# WS2812_MATRIX_8.net
KiCad netlist of a schematic drawn in Altium Designer
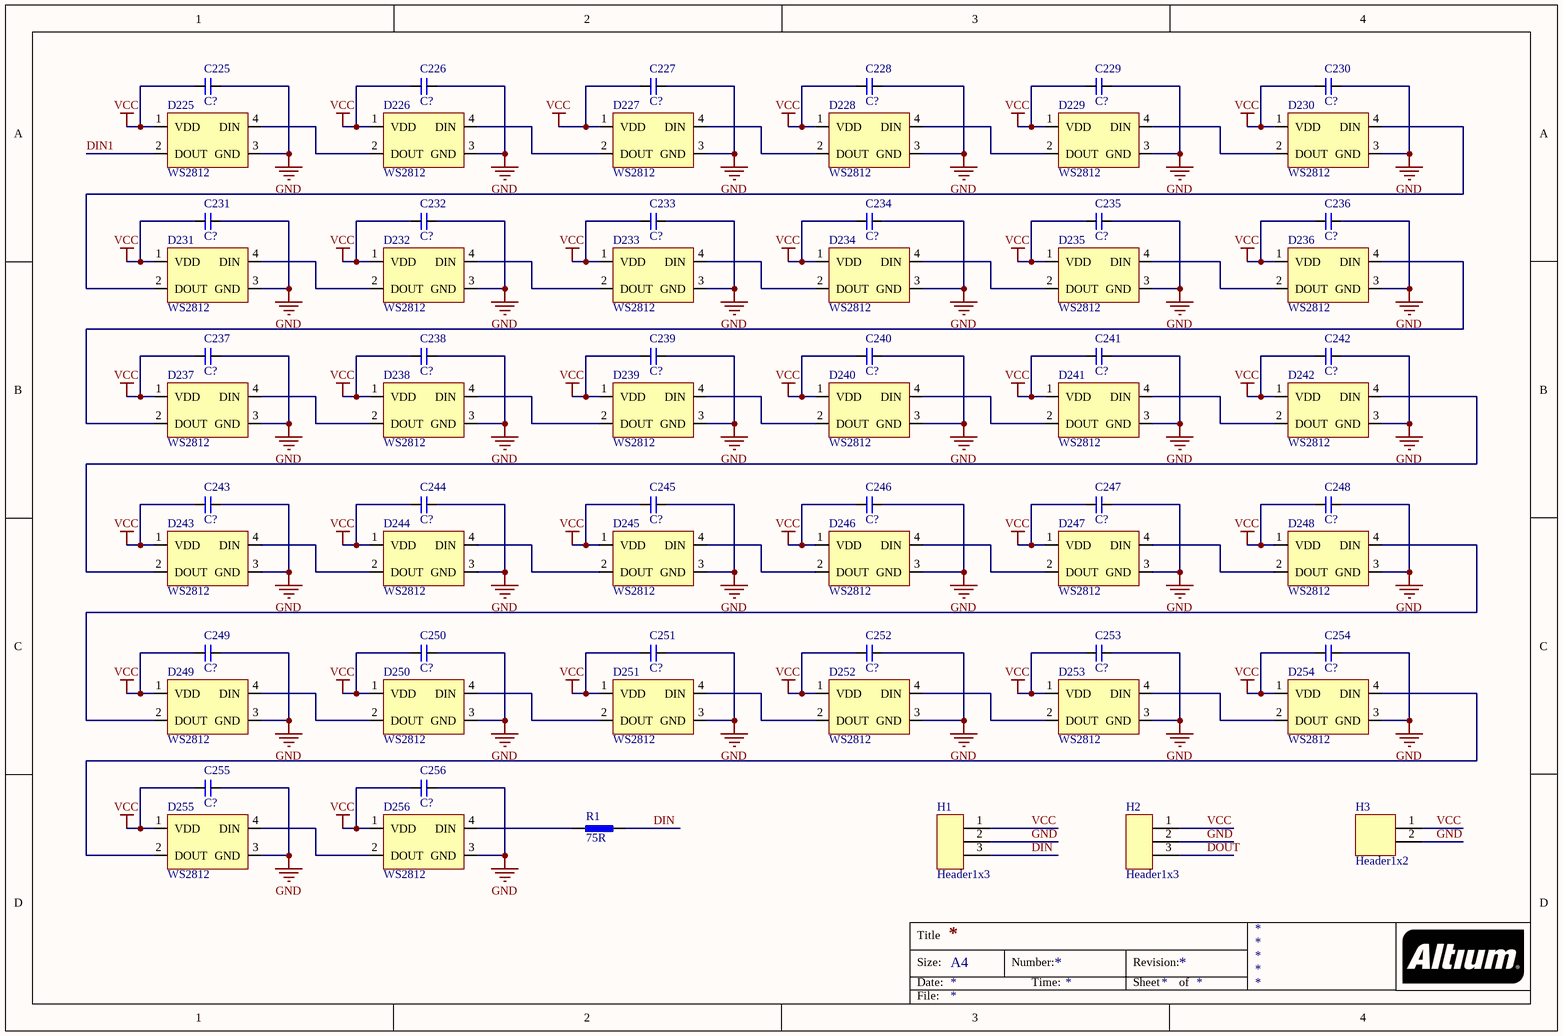
[diagram p0: WS2812_MATRIX_8.SchDoc]

(export (version "E")
  (design (tool "Eeschema 10.0.6"))
  (components
    (comp (ref "C225")
      (value "C?")
      (footprint "C0603")
      (description "Cap")
      (libsource (lib "SCH_Bacsic") (part "CAP"))
    )
    (comp (ref "C226")
      (value "C?")
      (footprint "C0603")
      (description "Cap")
      (libsource (lib "SCH_Bacsic") (part "CAP"))
    )
    (comp (ref "C227")
      (value "C?")
      (footprint "C0603")
      (description "Cap")
      (libsource (lib "SCH_Bacsic") (part "CAP"))
    )
    (comp (ref "C228")
      (value "C?")
      (footprint "C0603")
      (description "Cap")
      (libsource (lib "SCH_Bacsic") (part "CAP"))
    )
    (comp (ref "C229")
      (value "C?")
      (footprint "C0603")
      (description "Cap")
      (libsource (lib "SCH_Bacsic") (part "CAP"))
    )
    (comp (ref "C230")
      (value "C?")
      (footprint "C0603")
      (description "Cap")
      (libsource (lib "SCH_Bacsic") (part "CAP"))
    )
    (comp (ref "C231")
      (value "C?")
      (footprint "C0603")
      (description "Cap")
      (libsource (lib "SCH_Bacsic") (part "CAP"))
    )
    (comp (ref "C232")
      (value "C?")
      (footprint "C0603")
      (description "Cap")
      (libsource (lib "SCH_Bacsic") (part "CAP"))
    )
    (comp (ref "C233")
      (value "C?")
      (footprint "C0603")
      (description "Cap")
      (libsource (lib "SCH_Bacsic") (part "CAP"))
    )
    (comp (ref "C234")
      (value "C?")
      (footprint "C0603")
      (description "Cap")
      (libsource (lib "SCH_Bacsic") (part "CAP"))
    )
    (comp (ref "C235")
      (value "C?")
      (footprint "C0603")
      (description "Cap")
      (libsource (lib "SCH_Bacsic") (part "CAP"))
    )
    (comp (ref "C236")
      (value "C?")
      (footprint "C0603")
      (description "Cap")
      (libsource (lib "SCH_Bacsic") (part "CAP"))
    )
    (comp (ref "C237")
      (value "C?")
      (footprint "C0603")
      (description "Cap")
      (libsource (lib "SCH_Bacsic") (part "CAP"))
    )
    (comp (ref "C238")
      (value "C?")
      (footprint "C0603")
      (description "Cap")
      (libsource (lib "SCH_Bacsic") (part "CAP"))
    )
    (comp (ref "C239")
      (value "C?")
      (footprint "C0603")
      (description "Cap")
      (libsource (lib "SCH_Bacsic") (part "CAP"))
    )
    (comp (ref "C240")
      (value "C?")
      (footprint "C0603")
      (description "Cap")
      (libsource (lib "SCH_Bacsic") (part "CAP"))
    )
    (comp (ref "C241")
      (value "C?")
      (footprint "C0603")
      (description "Cap")
      (libsource (lib "SCH_Bacsic") (part "CAP"))
    )
    (comp (ref "C242")
      (value "C?")
      (footprint "C0603")
      (description "Cap")
      (libsource (lib "SCH_Bacsic") (part "CAP"))
    )
    (comp (ref "C243")
      (value "C?")
      (footprint "C0603")
      (description "Cap")
      (libsource (lib "SCH_Bacsic") (part "CAP"))
    )
    (comp (ref "C244")
      (value "C?")
      (footprint "C0603")
      (description "Cap")
      (libsource (lib "SCH_Bacsic") (part "CAP"))
    )
    (comp (ref "C245")
      (value "C?")
      (footprint "C0603")
      (description "Cap")
      (libsource (lib "SCH_Bacsic") (part "CAP"))
    )
    (comp (ref "C246")
      (value "C?")
      (footprint "C0603")
      (description "Cap")
      (libsource (lib "SCH_Bacsic") (part "CAP"))
    )
    (comp (ref "C247")
      (value "C?")
      (footprint "C0603")
      (description "Cap")
      (libsource (lib "SCH_Bacsic") (part "CAP"))
    )
    (comp (ref "C248")
      (value "C?")
      (footprint "C0603")
      (description "Cap")
      (libsource (lib "SCH_Bacsic") (part "CAP"))
    )
    (comp (ref "C249")
      (value "C?")
      (footprint "C0603")
      (description "Cap")
      (libsource (lib "SCH_Bacsic") (part "CAP"))
    )
    (comp (ref "C250")
      (value "C?")
      (footprint "C0603")
      (description "Cap")
      (libsource (lib "SCH_Bacsic") (part "CAP"))
    )
    (comp (ref "C251")
      (value "C?")
      (footprint "C0603")
      (description "Cap")
      (libsource (lib "SCH_Bacsic") (part "CAP"))
    )
    (comp (ref "C252")
      (value "C?")
      (footprint "C0603")
      (description "Cap")
      (libsource (lib "SCH_Bacsic") (part "CAP"))
    )
    (comp (ref "C253")
      (value "C?")
      (footprint "C0603")
      (description "Cap")
      (libsource (lib "SCH_Bacsic") (part "CAP"))
    )
    (comp (ref "C254")
      (value "C?")
      (footprint "C0603")
      (description "Cap")
      (libsource (lib "SCH_Bacsic") (part "CAP"))
    )
    (comp (ref "C255")
      (value "C?")
      (footprint "C0603")
      (description "Cap")
      (libsource (lib "SCH_Bacsic") (part "CAP"))
    )
    (comp (ref "C256")
      (value "C?")
      (footprint "C0603")
      (description "Cap")
      (libsource (lib "SCH_Bacsic") (part "CAP"))
    )
    (comp (ref "D225")
      (value "WS2812")
      (footprint "WS2812_3528")
      (libsource (lib "SCH_Bacsic") (part "WS2812"))
    )
    (comp (ref "D226")
      (value "WS2812")
      (footprint "WS2812_3528")
      (libsource (lib "SCH_Bacsic") (part "WS2812"))
    )
    (comp (ref "D227")
      (value "WS2812")
      (footprint "WS2812_3528")
      (libsource (lib "SCH_Bacsic") (part "WS2812"))
    )
    (comp (ref "D228")
      (value "WS2812")
      (footprint "WS2812_3528")
      (libsource (lib "SCH_Bacsic") (part "WS2812"))
    )
    (comp (ref "D229")
      (value "WS2812")
      (footprint "WS2812_3528")
      (libsource (lib "SCH_Bacsic") (part "WS2812"))
    )
    (comp (ref "D230")
      (value "WS2812")
      (footprint "WS2812_3528")
      (libsource (lib "SCH_Bacsic") (part "WS2812"))
    )
    (comp (ref "D231")
      (value "WS2812")
      (footprint "WS2812_3528")
      (libsource (lib "SCH_Bacsic") (part "WS2812"))
    )
    (comp (ref "D232")
      (value "WS2812")
      (footprint "WS2812_3528")
      (libsource (lib "SCH_Bacsic") (part "WS2812"))
    )
    (comp (ref "D233")
      (value "WS2812")
      (footprint "WS2812_3528")
      (libsource (lib "SCH_Bacsic") (part "WS2812"))
    )
    (comp (ref "D234")
      (value "WS2812")
      (footprint "WS2812_3528")
      (libsource (lib "SCH_Bacsic") (part "WS2812"))
    )
    (comp (ref "D235")
      (value "WS2812")
      (footprint "WS2812_3528")
      (libsource (lib "SCH_Bacsic") (part "WS2812"))
    )
    (comp (ref "D236")
      (value "WS2812")
      (footprint "WS2812_3528")
      (libsource (lib "SCH_Bacsic") (part "WS2812"))
    )
    (comp (ref "D237")
      (value "WS2812")
      (footprint "WS2812_3528")
      (libsource (lib "SCH_Bacsic") (part "WS2812"))
    )
    (comp (ref "D238")
      (value "WS2812")
      (footprint "WS2812_3528")
      (libsource (lib "SCH_Bacsic") (part "WS2812"))
    )
    (comp (ref "D239")
      (value "WS2812")
      (footprint "WS2812_3528")
      (libsource (lib "SCH_Bacsic") (part "WS2812"))
    )
    (comp (ref "D240")
      (value "WS2812")
      (footprint "WS2812_3528")
      (libsource (lib "SCH_Bacsic") (part "WS2812"))
    )
    (comp (ref "D241")
      (value "WS2812")
      (footprint "WS2812_3528")
      (libsource (lib "SCH_Bacsic") (part "WS2812"))
    )
    (comp (ref "D242")
      (value "WS2812")
      (footprint "WS2812_3528")
      (libsource (lib "SCH_Bacsic") (part "WS2812"))
    )
    (comp (ref "D243")
      (value "WS2812")
      (footprint "WS2812_3528")
      (libsource (lib "SCH_Bacsic") (part "WS2812"))
    )
    (comp (ref "D244")
      (value "WS2812")
      (footprint "WS2812_3528")
      (libsource (lib "SCH_Bacsic") (part "WS2812"))
    )
    (comp (ref "D245")
      (value "WS2812")
      (footprint "WS2812_3528")
      (libsource (lib "SCH_Bacsic") (part "WS2812"))
    )
    (comp (ref "D246")
      (value "WS2812")
      (footprint "WS2812_3528")
      (libsource (lib "SCH_Bacsic") (part "WS2812"))
    )
    (comp (ref "D247")
      (value "WS2812")
      (footprint "WS2812_3528")
      (libsource (lib "SCH_Bacsic") (part "WS2812"))
    )
    (comp (ref "D248")
      (value "WS2812")
      (footprint "WS2812_3528")
      (libsource (lib "SCH_Bacsic") (part "WS2812"))
    )
    (comp (ref "D249")
      (value "WS2812")
      (footprint "WS2812_3528")
      (libsource (lib "SCH_Bacsic") (part "WS2812"))
    )
    (comp (ref "D250")
      (value "WS2812")
      (footprint "WS2812_3528")
      (libsource (lib "SCH_Bacsic") (part "WS2812"))
    )
    (comp (ref "D251")
      (value "WS2812")
      (footprint "WS2812_3528")
      (libsource (lib "SCH_Bacsic") (part "WS2812"))
    )
    (comp (ref "D252")
      (value "WS2812")
      (footprint "WS2812_3528")
      (libsource (lib "SCH_Bacsic") (part "WS2812"))
    )
    (comp (ref "D253")
      (value "WS2812")
      (footprint "WS2812_3528")
      (libsource (lib "SCH_Bacsic") (part "WS2812"))
    )
    (comp (ref "D254")
      (value "WS2812")
      (footprint "WS2812_3528")
      (libsource (lib "SCH_Bacsic") (part "WS2812"))
    )
    (comp (ref "D255")
      (value "WS2812")
      (footprint "WS2812_3528")
      (libsource (lib "SCH_Bacsic") (part "WS2812"))
    )
    (comp (ref "D256")
      (value "WS2812")
      (footprint "WS2812_3528")
      (libsource (lib "SCH_Bacsic") (part "WS2812"))
    )
    (comp (ref "H1")
      (value "Header1x3")
      (footprint "HDR1X3_2.54_NO_HOLE")
      (libsource (lib "SCH_Connector") (part "Header1x3"))
    )
    (comp (ref "H2")
      (value "Header1x3")
      (footprint "HDR1X3_2.54_NO_HOLE")
      (libsource (lib "SCH_Connector") (part "Header1x3"))
    )
    (comp (ref "H3")
      (value "Header1x2")
      (footprint "BATIN")
      (libsource (lib "SCH_Connector") (part "Header1x2"))
    )
    (comp (ref "R1") (value "75R") (footprint "R0603") (libsource (lib "SCH_Bacsic") (part "RES")))
  )
  (nets
    (net (code "1") (name "/DIN") (class "Default")
      (node (ref "H1") (pin "3") (pintype "passive"))
      (node (ref "R1") (pin "2") (pintype "passive"))
    )
    (net (code "2") (name "/DIN1") (class "Default")
      (node (ref "D225") (pin "2") (pinfunction "DOUT_2") (pintype "passive"))
    )
    (net (code "3") (name "/DOUT") (class "Default") (node (ref "H2") (pin "3") (pintype "passive")))
    (net (code "4") (name "GND") (class "Default")
      (node (ref "C225") (pin "2") (pintype "passive"))
      (node (ref "C226") (pin "2") (pintype "passive"))
      (node (ref "C227") (pin "2") (pintype "passive"))
      (node (ref "C228") (pin "2") (pintype "passive"))
      (node (ref "C229") (pin "2") (pintype "passive"))
      (node (ref "C230") (pin "2") (pintype "passive"))
      (node (ref "C231") (pin "2") (pintype "passive"))
      (node (ref "C232") (pin "2") (pintype "passive"))
      (node (ref "C233") (pin "2") (pintype "passive"))
      (node (ref "C234") (pin "2") (pintype "passive"))
      (node (ref "C235") (pin "2") (pintype "passive"))
      (node (ref "C236") (pin "2") (pintype "passive"))
      (node (ref "C237") (pin "2") (pintype "passive"))
      (node (ref "C238") (pin "2") (pintype "passive"))
      (node (ref "C239") (pin "2") (pintype "passive"))
      (node (ref "C240") (pin "2") (pintype "passive"))
      (node (ref "C241") (pin "2") (pintype "passive"))
      (node (ref "C242") (pin "2") (pintype "passive"))
      (node (ref "C243") (pin "2") (pintype "passive"))
      (node (ref "C244") (pin "2") (pintype "passive"))
      (node (ref "C245") (pin "2") (pintype "passive"))
      (node (ref "C246") (pin "2") (pintype "passive"))
      (node (ref "C247") (pin "2") (pintype "passive"))
      (node (ref "C248") (pin "2") (pintype "passive"))
      (node (ref "C249") (pin "2") (pintype "passive"))
      (node (ref "C250") (pin "2") (pintype "passive"))
      (node (ref "C251") (pin "2") (pintype "passive"))
      (node (ref "C252") (pin "2") (pintype "passive"))
      (node (ref "C253") (pin "2") (pintype "passive"))
      (node (ref "C254") (pin "2") (pintype "passive"))
      (node (ref "C255") (pin "2") (pintype "passive"))
      (node (ref "C256") (pin "2") (pintype "passive"))
      (node (ref "D225") (pin "3") (pinfunction "GND_3") (pintype "passive"))
      (node (ref "D226") (pin "3") (pinfunction "GND_3") (pintype "passive"))
      (node (ref "D227") (pin "3") (pinfunction "GND_3") (pintype "passive"))
      (node (ref "D228") (pin "3") (pinfunction "GND_3") (pintype "passive"))
      (node (ref "D229") (pin "3") (pinfunction "GND_3") (pintype "passive"))
      (node (ref "D230") (pin "3") (pinfunction "GND_3") (pintype "passive"))
      (node (ref "D231") (pin "3") (pinfunction "GND_3") (pintype "passive"))
      (node (ref "D232") (pin "3") (pinfunction "GND_3") (pintype "passive"))
      (node (ref "D233") (pin "3") (pinfunction "GND_3") (pintype "passive"))
      (node (ref "D234") (pin "3") (pinfunction "GND_3") (pintype "passive"))
      (node (ref "D235") (pin "3") (pinfunction "GND_3") (pintype "passive"))
      (node (ref "D236") (pin "3") (pinfunction "GND_3") (pintype "passive"))
      (node (ref "D237") (pin "3") (pinfunction "GND_3") (pintype "passive"))
      (node (ref "D238") (pin "3") (pinfunction "GND_3") (pintype "passive"))
      (node (ref "D239") (pin "3") (pinfunction "GND_3") (pintype "passive"))
      (node (ref "D240") (pin "3") (pinfunction "GND_3") (pintype "passive"))
      (node (ref "D241") (pin "3") (pinfunction "GND_3") (pintype "passive"))
      (node (ref "D242") (pin "3") (pinfunction "GND_3") (pintype "passive"))
      (node (ref "D243") (pin "3") (pinfunction "GND_3") (pintype "passive"))
      (node (ref "D244") (pin "3") (pinfunction "GND_3") (pintype "passive"))
      (node (ref "D245") (pin "3") (pinfunction "GND_3") (pintype "passive"))
      (node (ref "D246") (pin "3") (pinfunction "GND_3") (pintype "passive"))
      (node (ref "D247") (pin "3") (pinfunction "GND_3") (pintype "passive"))
      (node (ref "D248") (pin "3") (pinfunction "GND_3") (pintype "passive"))
      (node (ref "D249") (pin "3") (pinfunction "GND_3") (pintype "passive"))
      (node (ref "D250") (pin "3") (pinfunction "GND_3") (pintype "passive"))
      (node (ref "D251") (pin "3") (pinfunction "GND_3") (pintype "passive"))
      (node (ref "D252") (pin "3") (pinfunction "GND_3") (pintype "passive"))
      (node (ref "D253") (pin "3") (pinfunction "GND_3") (pintype "passive"))
      (node (ref "D254") (pin "3") (pinfunction "GND_3") (pintype "passive"))
      (node (ref "D255") (pin "3") (pinfunction "GND_3") (pintype "passive"))
      (node (ref "D256") (pin "3") (pinfunction "GND_3") (pintype "passive"))
      (node (ref "H1") (pin "2") (pintype "passive"))
      (node (ref "H2") (pin "2") (pintype "passive"))
      (node (ref "H3") (pin "2") (pintype "passive"))
    )
    (net (code "5") (name "Net-(D225-DIN)") (class "Default")
      (node (ref "D225") (pin "4") (pinfunction "DIN_4") (pintype "passive"))
      (node (ref "D226") (pin "2") (pinfunction "DOUT_2") (pintype "passive"))
    )
    (net (code "6") (name "Net-(D226-DIN)") (class "Default")
      (node (ref "D226") (pin "4") (pinfunction "DIN_4") (pintype "passive"))
      (node (ref "D227") (pin "2") (pinfunction "DOUT_2") (pintype "passive"))
    )
    (net (code "7") (name "Net-(D227-DIN)") (class "Default")
      (node (ref "D227") (pin "4") (pinfunction "DIN_4") (pintype "passive"))
      (node (ref "D228") (pin "2") (pinfunction "DOUT_2") (pintype "passive"))
    )
    (net (code "8") (name "Net-(D228-DIN)") (class "Default")
      (node (ref "D228") (pin "4") (pinfunction "DIN_4") (pintype "passive"))
      (node (ref "D229") (pin "2") (pinfunction "DOUT_2") (pintype "passive"))
    )
    (net (code "9") (name "Net-(D229-DIN)") (class "Default")
      (node (ref "D229") (pin "4") (pinfunction "DIN_4") (pintype "passive"))
      (node (ref "D230") (pin "2") (pinfunction "DOUT_2") (pintype "passive"))
    )
    (net (code "10") (name "Net-(D230-DIN)") (class "Default")
      (node (ref "D230") (pin "4") (pinfunction "DIN_4") (pintype "passive"))
      (node (ref "D231") (pin "2") (pinfunction "DOUT_2") (pintype "passive"))
    )
    (net (code "11") (name "Net-(D231-DIN)") (class "Default")
      (node (ref "D231") (pin "4") (pinfunction "DIN_4") (pintype "passive"))
      (node (ref "D232") (pin "2") (pinfunction "DOUT_2") (pintype "passive"))
    )
    (net (code "12") (name "Net-(D232-DIN)") (class "Default")
      (node (ref "D232") (pin "4") (pinfunction "DIN_4") (pintype "passive"))
      (node (ref "D233") (pin "2") (pinfunction "DOUT_2") (pintype "passive"))
    )
    (net (code "13") (name "Net-(D233-DIN)") (class "Default")
      (node (ref "D233") (pin "4") (pinfunction "DIN_4") (pintype "passive"))
      (node (ref "D234") (pin "2") (pinfunction "DOUT_2") (pintype "passive"))
    )
    (net (code "14") (name "Net-(D234-DIN)") (class "Default")
      (node (ref "D234") (pin "4") (pinfunction "DIN_4") (pintype "passive"))
      (node (ref "D235") (pin "2") (pinfunction "DOUT_2") (pintype "passive"))
    )
    (net (code "15") (name "Net-(D235-DIN)") (class "Default")
      (node (ref "D235") (pin "4") (pinfunction "DIN_4") (pintype "passive"))
      (node (ref "D236") (pin "2") (pinfunction "DOUT_2") (pintype "passive"))
    )
    (net (code "16") (name "Net-(D236-DIN)") (class "Default")
      (node (ref "D236") (pin "4") (pinfunction "DIN_4") (pintype "passive"))
      (node (ref "D237") (pin "2") (pinfunction "DOUT_2") (pintype "passive"))
    )
    (net (code "17") (name "Net-(D237-DIN)") (class "Default")
      (node (ref "D237") (pin "4") (pinfunction "DIN_4") (pintype "passive"))
      (node (ref "D238") (pin "2") (pinfunction "DOUT_2") (pintype "passive"))
    )
    (net (code "18") (name "Net-(D238-DIN)") (class "Default")
      (node (ref "D238") (pin "4") (pinfunction "DIN_4") (pintype "passive"))
      (node (ref "D239") (pin "2") (pinfunction "DOUT_2") (pintype "passive"))
    )
    (net (code "19") (name "Net-(D239-DIN)") (class "Default")
      (node (ref "D239") (pin "4") (pinfunction "DIN_4") (pintype "passive"))
      (node (ref "D240") (pin "2") (pinfunction "DOUT_2") (pintype "passive"))
    )
    (net (code "20") (name "Net-(D240-DIN)") (class "Default")
      (node (ref "D240") (pin "4") (pinfunction "DIN_4") (pintype "passive"))
      (node (ref "D241") (pin "2") (pinfunction "DOUT_2") (pintype "passive"))
    )
    (net (code "21") (name "Net-(D241-DIN)") (class "Default")
      (node (ref "D241") (pin "4") (pinfunction "DIN_4") (pintype "passive"))
      (node (ref "D242") (pin "2") (pinfunction "DOUT_2") (pintype "passive"))
    )
    (net (code "22") (name "Net-(D242-DIN)") (class "Default")
      (node (ref "D242") (pin "4") (pinfunction "DIN_4") (pintype "passive"))
      (node (ref "D243") (pin "2") (pinfunction "DOUT_2") (pintype "passive"))
    )
    (net (code "23") (name "Net-(D243-DIN)") (class "Default")
      (node (ref "D243") (pin "4") (pinfunction "DIN_4") (pintype "passive"))
      (node (ref "D244") (pin "2") (pinfunction "DOUT_2") (pintype "passive"))
    )
    (net (code "24") (name "Net-(D244-DIN)") (class "Default")
      (node (ref "D244") (pin "4") (pinfunction "DIN_4") (pintype "passive"))
      (node (ref "D245") (pin "2") (pinfunction "DOUT_2") (pintype "passive"))
    )
    (net (code "25") (name "Net-(D245-DIN)") (class "Default")
      (node (ref "D245") (pin "4") (pinfunction "DIN_4") (pintype "passive"))
      (node (ref "D246") (pin "2") (pinfunction "DOUT_2") (pintype "passive"))
    )
    (net (code "26") (name "Net-(D246-DIN)") (class "Default")
      (node (ref "D246") (pin "4") (pinfunction "DIN_4") (pintype "passive"))
      (node (ref "D247") (pin "2") (pinfunction "DOUT_2") (pintype "passive"))
    )
    (net (code "27") (name "Net-(D247-DIN)") (class "Default")
      (node (ref "D247") (pin "4") (pinfunction "DIN_4") (pintype "passive"))
      (node (ref "D248") (pin "2") (pinfunction "DOUT_2") (pintype "passive"))
    )
    (net (code "28") (name "Net-(D248-DIN)") (class "Default")
      (node (ref "D248") (pin "4") (pinfunction "DIN_4") (pintype "passive"))
      (node (ref "D249") (pin "2") (pinfunction "DOUT_2") (pintype "passive"))
    )
    (net (code "29") (name "Net-(D249-DIN)") (class "Default")
      (node (ref "D249") (pin "4") (pinfunction "DIN_4") (pintype "passive"))
      (node (ref "D250") (pin "2") (pinfunction "DOUT_2") (pintype "passive"))
    )
    (net (code "30") (name "Net-(D250-DIN)") (class "Default")
      (node (ref "D250") (pin "4") (pinfunction "DIN_4") (pintype "passive"))
      (node (ref "D251") (pin "2") (pinfunction "DOUT_2") (pintype "passive"))
    )
    (net (code "31") (name "Net-(D251-DIN)") (class "Default")
      (node (ref "D251") (pin "4") (pinfunction "DIN_4") (pintype "passive"))
      (node (ref "D252") (pin "2") (pinfunction "DOUT_2") (pintype "passive"))
    )
    (net (code "32") (name "Net-(D252-DIN)") (class "Default")
      (node (ref "D252") (pin "4") (pinfunction "DIN_4") (pintype "passive"))
      (node (ref "D253") (pin "2") (pinfunction "DOUT_2") (pintype "passive"))
    )
    (net (code "33") (name "Net-(D253-DIN)") (class "Default")
      (node (ref "D253") (pin "4") (pinfunction "DIN_4") (pintype "passive"))
      (node (ref "D254") (pin "2") (pinfunction "DOUT_2") (pintype "passive"))
    )
    (net (code "34") (name "Net-(D254-DIN)") (class "Default")
      (node (ref "D254") (pin "4") (pinfunction "DIN_4") (pintype "passive"))
      (node (ref "D255") (pin "2") (pinfunction "DOUT_2") (pintype "passive"))
    )
    (net (code "35") (name "Net-(D255-DIN)") (class "Default")
      (node (ref "D255") (pin "4") (pinfunction "DIN_4") (pintype "passive"))
      (node (ref "D256") (pin "2") (pinfunction "DOUT_2") (pintype "passive"))
    )
    (net (code "36") (name "Net-(D256-DIN)") (class "Default")
      (node (ref "D256") (pin "4") (pinfunction "DIN_4") (pintype "passive"))
      (node (ref "R1") (pin "1") (pintype "passive"))
    )
    (net (code "37") (name "VCC") (class "Default")
      (node (ref "C225") (pin "1") (pintype "passive"))
      (node (ref "C226") (pin "1") (pintype "passive"))
      (node (ref "C227") (pin "1") (pintype "passive"))
      (node (ref "C228") (pin "1") (pintype "passive"))
      (node (ref "C229") (pin "1") (pintype "passive"))
      (node (ref "C230") (pin "1") (pintype "passive"))
      (node (ref "C231") (pin "1") (pintype "passive"))
      (node (ref "C232") (pin "1") (pintype "passive"))
      (node (ref "C233") (pin "1") (pintype "passive"))
      (node (ref "C234") (pin "1") (pintype "passive"))
      (node (ref "C235") (pin "1") (pintype "passive"))
      (node (ref "C236") (pin "1") (pintype "passive"))
      (node (ref "C237") (pin "1") (pintype "passive"))
      (node (ref "C238") (pin "1") (pintype "passive"))
      (node (ref "C239") (pin "1") (pintype "passive"))
      (node (ref "C240") (pin "1") (pintype "passive"))
      (node (ref "C241") (pin "1") (pintype "passive"))
      (node (ref "C242") (pin "1") (pintype "passive"))
      (node (ref "C243") (pin "1") (pintype "passive"))
      (node (ref "C244") (pin "1") (pintype "passive"))
      (node (ref "C245") (pin "1") (pintype "passive"))
      (node (ref "C246") (pin "1") (pintype "passive"))
      (node (ref "C247") (pin "1") (pintype "passive"))
      (node (ref "C248") (pin "1") (pintype "passive"))
      (node (ref "C249") (pin "1") (pintype "passive"))
      (node (ref "C250") (pin "1") (pintype "passive"))
      (node (ref "C251") (pin "1") (pintype "passive"))
      (node (ref "C252") (pin "1") (pintype "passive"))
      (node (ref "C253") (pin "1") (pintype "passive"))
      (node (ref "C254") (pin "1") (pintype "passive"))
      (node (ref "C255") (pin "1") (pintype "passive"))
      (node (ref "C256") (pin "1") (pintype "passive"))
      (node (ref "D225") (pin "1") (pinfunction "VDD_1") (pintype "passive"))
      (node (ref "D226") (pin "1") (pinfunction "VDD_1") (pintype "passive"))
      (node (ref "D227") (pin "1") (pinfunction "VDD_1") (pintype "passive"))
      (node (ref "D228") (pin "1") (pinfunction "VDD_1") (pintype "passive"))
      (node (ref "D229") (pin "1") (pinfunction "VDD_1") (pintype "passive"))
      (node (ref "D230") (pin "1") (pinfunction "VDD_1") (pintype "passive"))
      (node (ref "D231") (pin "1") (pinfunction "VDD_1") (pintype "passive"))
      (node (ref "D232") (pin "1") (pinfunction "VDD_1") (pintype "passive"))
      (node (ref "D233") (pin "1") (pinfunction "VDD_1") (pintype "passive"))
      (node (ref "D234") (pin "1") (pinfunction "VDD_1") (pintype "passive"))
      (node (ref "D235") (pin "1") (pinfunction "VDD_1") (pintype "passive"))
      (node (ref "D236") (pin "1") (pinfunction "VDD_1") (pintype "passive"))
      (node (ref "D237") (pin "1") (pinfunction "VDD_1") (pintype "passive"))
      (node (ref "D238") (pin "1") (pinfunction "VDD_1") (pintype "passive"))
      (node (ref "D239") (pin "1") (pinfunction "VDD_1") (pintype "passive"))
      (node (ref "D240") (pin "1") (pinfunction "VDD_1") (pintype "passive"))
      (node (ref "D241") (pin "1") (pinfunction "VDD_1") (pintype "passive"))
      (node (ref "D242") (pin "1") (pinfunction "VDD_1") (pintype "passive"))
      (node (ref "D243") (pin "1") (pinfunction "VDD_1") (pintype "passive"))
      (node (ref "D244") (pin "1") (pinfunction "VDD_1") (pintype "passive"))
      (node (ref "D245") (pin "1") (pinfunction "VDD_1") (pintype "passive"))
      (node (ref "D246") (pin "1") (pinfunction "VDD_1") (pintype "passive"))
      (node (ref "D247") (pin "1") (pinfunction "VDD_1") (pintype "passive"))
      (node (ref "D248") (pin "1") (pinfunction "VDD_1") (pintype "passive"))
      (node (ref "D249") (pin "1") (pinfunction "VDD_1") (pintype "passive"))
      (node (ref "D250") (pin "1") (pinfunction "VDD_1") (pintype "passive"))
      (node (ref "D251") (pin "1") (pinfunction "VDD_1") (pintype "passive"))
      (node (ref "D252") (pin "1") (pinfunction "VDD_1") (pintype "passive"))
      (node (ref "D253") (pin "1") (pinfunction "VDD_1") (pintype "passive"))
      (node (ref "D254") (pin "1") (pinfunction "VDD_1") (pintype "passive"))
      (node (ref "D255") (pin "1") (pinfunction "VDD_1") (pintype "passive"))
      (node (ref "D256") (pin "1") (pinfunction "VDD_1") (pintype "passive"))
      (node (ref "H1") (pin "1") (pintype "passive"))
      (node (ref "H2") (pin "1") (pintype "passive"))
      (node (ref "H3") (pin "1") (pintype "passive"))
    )
  )
)
